# CPLD.net
KiCad netlist of a schematic drawn in Altium Designer
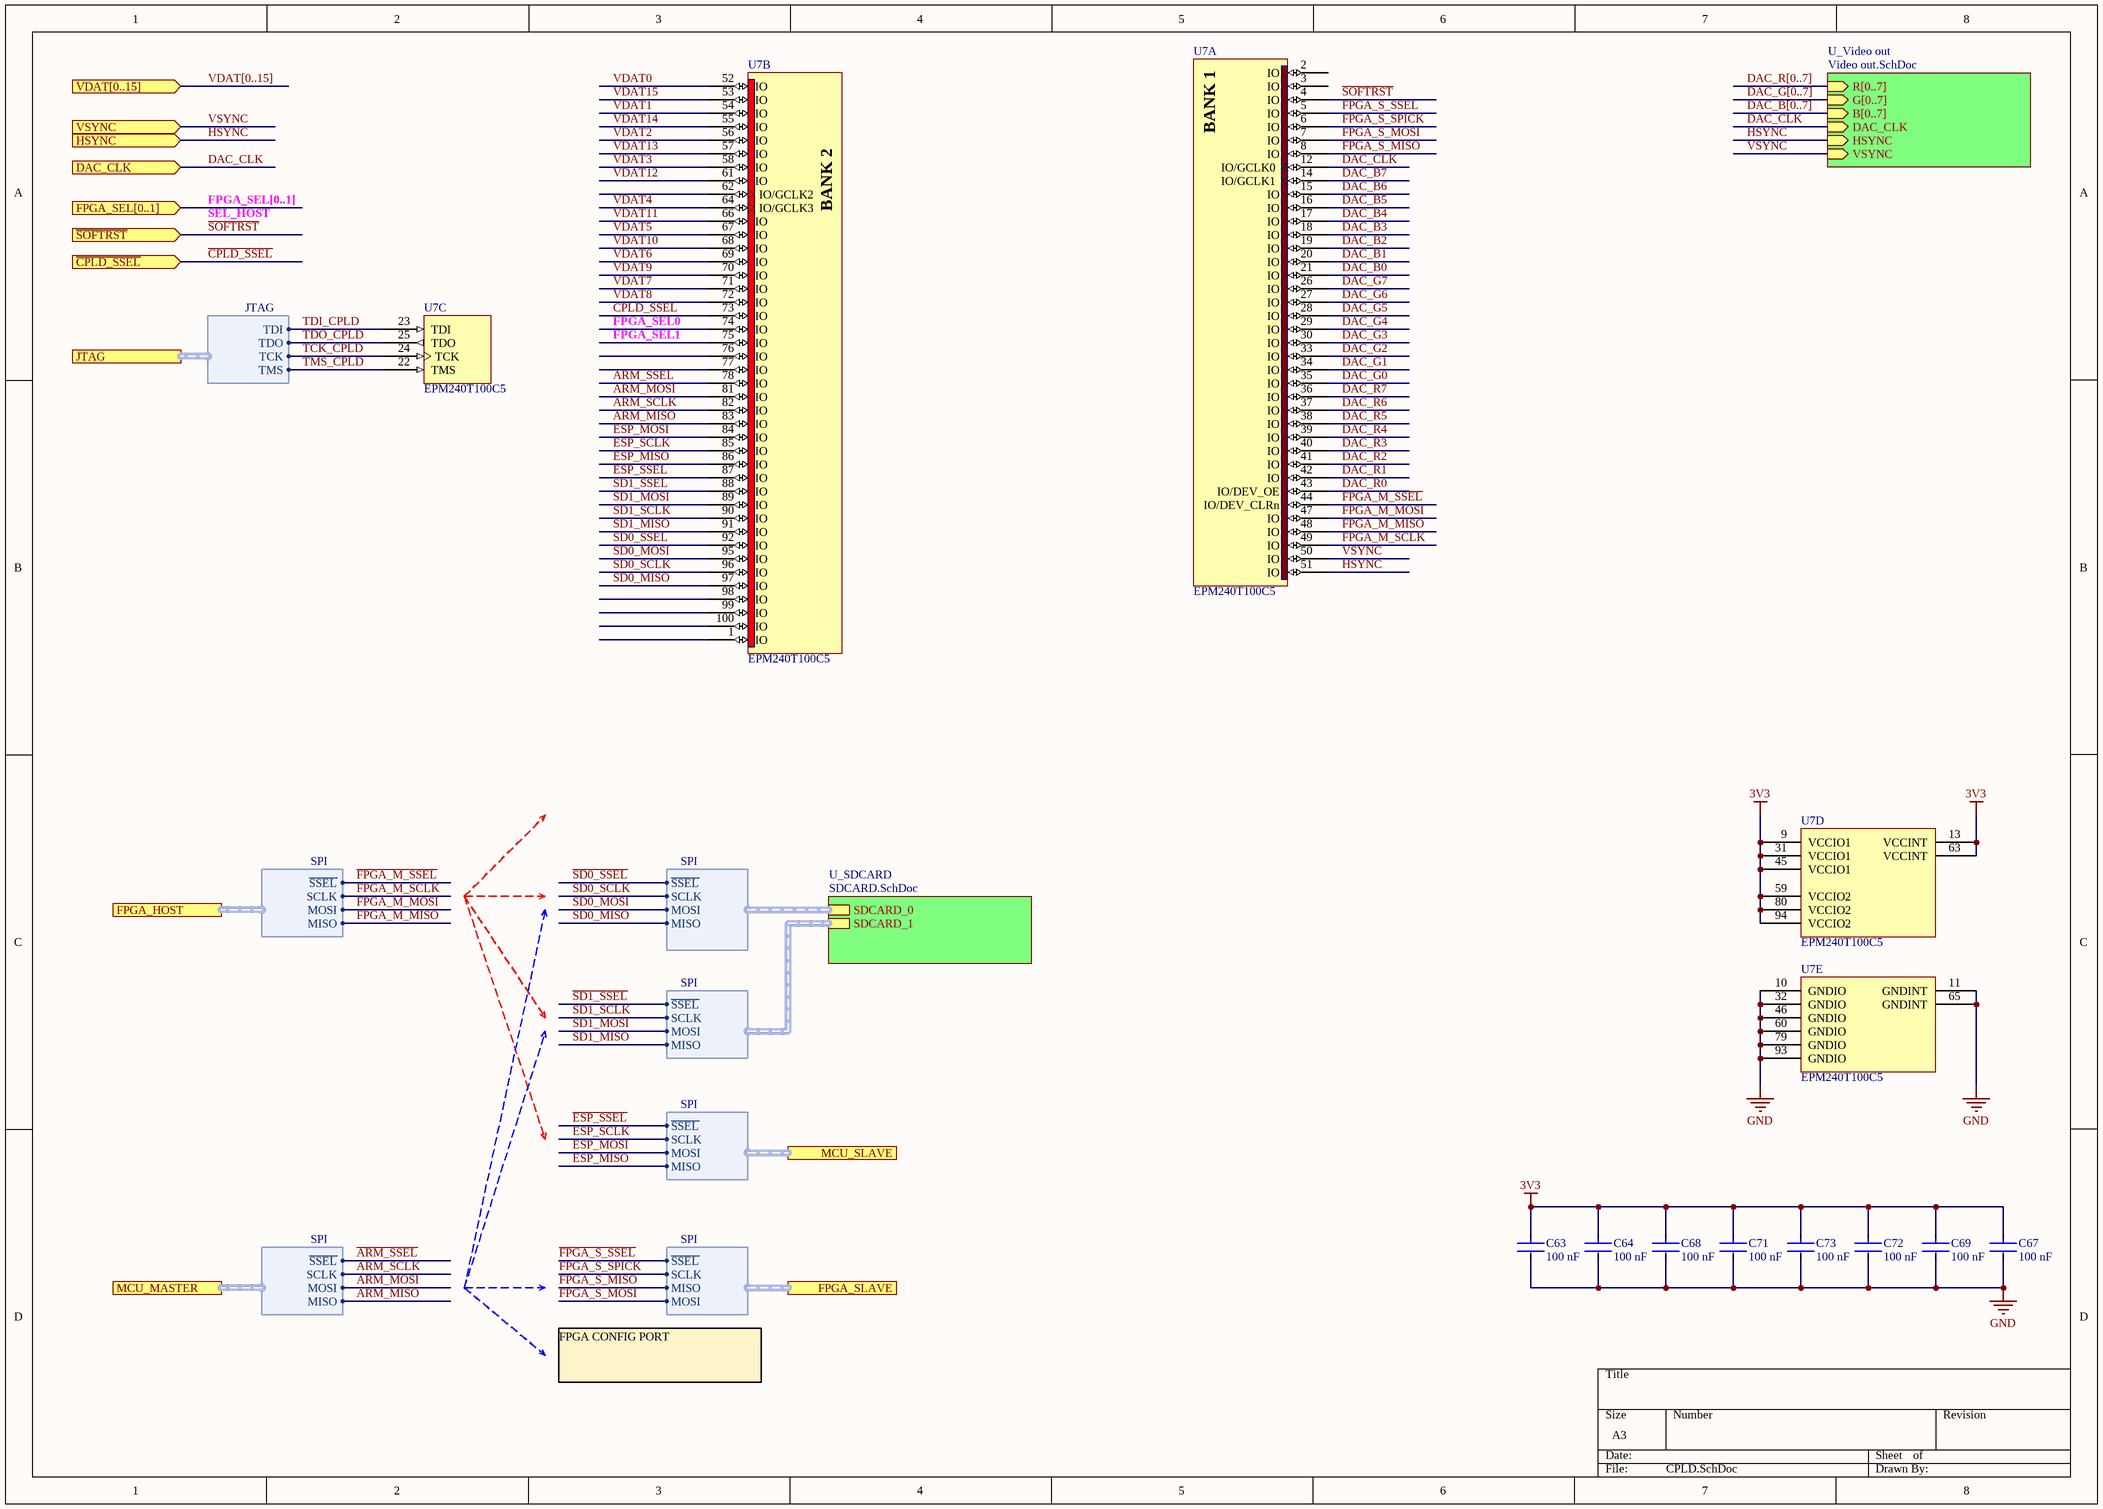
[diagram p0: CPLD.SchDoc]

(export (version "E")
  (design (tool "Eeschema 10.0.6"))
  (components
    (comp (ref "C63")
      (value "CC0805KRX7R9BB104")
      (footprint "FP-CC0805-0_85-IPC_A")
      (description "CAP CER 0.1UF 50V X7R 0805")
      (fields (field (name "MANUFACTURER") "Yageo") (field (name "CAPACITANCE") "100 nF"))
      (libsource (lib "SchLib") (part "CMP-2100-03606-3"))
    )
    (comp (ref "C64")
      (value "CC0805KRX7R9BB104")
      (footprint "FP-CC0805-0_85-IPC_A")
      (description "CAP CER 0.1UF 50V X7R 0805")
      (fields (field (name "MANUFACTURER") "Yageo") (field (name "CAPACITANCE") "100 nF"))
      (libsource (lib "SchLib") (part "CMP-2100-03606-3"))
    )
    (comp (ref "C67")
      (value "CC0805KRX7R9BB104")
      (footprint "FP-CC0805-0_85-IPC_A")
      (description "CAP CER 0.1UF 50V X7R 0805")
      (fields (field (name "MANUFACTURER") "Yageo") (field (name "CAPACITANCE") "100 nF"))
      (libsource (lib "SchLib") (part "CMP-2100-03606-3"))
    )
    (comp (ref "C68")
      (value "CC0805KRX7R9BB104")
      (footprint "FP-CC0805-0_85-IPC_A")
      (description "CAP CER 0.1UF 50V X7R 0805")
      (fields (field (name "MANUFACTURER") "Yageo") (field (name "CAPACITANCE") "100 nF"))
      (libsource (lib "SchLib") (part "CMP-2100-03606-3"))
    )
    (comp (ref "C69")
      (value "CC0805KRX7R9BB104")
      (footprint "FP-CC0805-0_85-IPC_A")
      (description "CAP CER 0.1UF 50V X7R 0805")
      (fields (field (name "MANUFACTURER") "Yageo") (field (name "CAPACITANCE") "100 nF"))
      (libsource (lib "SchLib") (part "CMP-2100-03606-3"))
    )
    (comp (ref "C71")
      (value "CC0805KRX7R9BB104")
      (footprint "FP-CC0805-0_85-IPC_A")
      (description "CAP CER 0.1UF 50V X7R 0805")
      (fields (field (name "MANUFACTURER") "Yageo") (field (name "CAPACITANCE") "100 nF"))
      (libsource (lib "SchLib") (part "CMP-2100-03606-3"))
    )
    (comp (ref "C72")
      (value "CC0805KRX7R9BB104")
      (footprint "FP-CC0805-0_85-IPC_A")
      (description "CAP CER 0.1UF 50V X7R 0805")
      (fields (field (name "MANUFACTURER") "Yageo") (field (name "CAPACITANCE") "100 nF"))
      (libsource (lib "SchLib") (part "CMP-2100-03606-3"))
    )
    (comp (ref "C73")
      (value "CC0805KRX7R9BB104")
      (footprint "FP-CC0805-0_85-IPC_A")
      (description "CAP CER 0.1UF 50V X7R 0805")
      (fields (field (name "MANUFACTURER") "Yageo") (field (name "CAPACITANCE") "100 nF"))
      (libsource (lib "SchLib") (part "CMP-2100-03606-3"))
    )
    (comp (ref "U7")
      (value "EPM240T100C5")
      (footprint "TQFP100_M")
      (fields (field (name "MANUFACTURER") "Intel Altera"))
      (libsource (lib "") (part "CMP-0144-00216-1_1"))
    )
  )
  (nets
    (net (code "3") (name "/ARM_MISO") (class "Default")
      (node (ref "U7") (pin "83") (pinfunction "IO_83") (pintype "bidirectional"))
    )
    (net (code "4") (name "/ARM_MOSI") (class "Default")
      (node (ref "U7") (pin "81") (pinfunction "IO_81") (pintype "bidirectional"))
    )
    (net (code "5") (name "/ARM_SCLK") (class "Default")
      (node (ref "U7") (pin "82") (pinfunction "IO_82") (pintype "bidirectional"))
    )
    (net (code "6") (name "/DAC_B0") (class "Default")
      (node (ref "U7") (pin "21") (pinfunction "IO_21") (pintype "bidirectional"))
    )
    (net (code "7") (name "/DAC_B1") (class "Default")
      (node (ref "U7") (pin "20") (pinfunction "IO_20") (pintype "bidirectional"))
    )
    (net (code "8") (name "/DAC_B2") (class "Default")
      (node (ref "U7") (pin "19") (pinfunction "IO_19") (pintype "bidirectional"))
    )
    (net (code "9") (name "/DAC_B3") (class "Default")
      (node (ref "U7") (pin "18") (pinfunction "IO_18") (pintype "bidirectional"))
    )
    (net (code "10") (name "/DAC_B4") (class "Default")
      (node (ref "U7") (pin "17") (pinfunction "IO_17") (pintype "bidirectional"))
    )
    (net (code "11") (name "/DAC_B5") (class "Default")
      (node (ref "U7") (pin "16") (pinfunction "IO_16") (pintype "bidirectional"))
    )
    (net (code "12") (name "/DAC_B6") (class "Default")
      (node (ref "U7") (pin "15") (pinfunction "IO_15") (pintype "bidirectional"))
    )
    (net (code "13") (name "/DAC_B7") (class "Default")
      (node (ref "U7") (pin "14") (pinfunction "IO/GCLK1_14") (pintype "bidirectional"))
    )
    (net (code "15") (name "/DAC_CLK") (class "Default")
      (node (ref "U7") (pin "12") (pinfunction "IO/GCLK0_12") (pintype "bidirectional"))
    )
    (net (code "16") (name "/DAC_G0") (class "Default")
      (node (ref "U7") (pin "35") (pinfunction "IO_35") (pintype "bidirectional"))
    )
    (net (code "17") (name "/DAC_G1") (class "Default")
      (node (ref "U7") (pin "34") (pinfunction "IO_34") (pintype "bidirectional"))
    )
    (net (code "18") (name "/DAC_G2") (class "Default")
      (node (ref "U7") (pin "33") (pinfunction "IO_33") (pintype "bidirectional"))
    )
    (net (code "19") (name "/DAC_G3") (class "Default")
      (node (ref "U7") (pin "30") (pinfunction "IO_30") (pintype "bidirectional"))
    )
    (net (code "20") (name "/DAC_G4") (class "Default")
      (node (ref "U7") (pin "29") (pinfunction "IO_29") (pintype "bidirectional"))
    )
    (net (code "21") (name "/DAC_G5") (class "Default")
      (node (ref "U7") (pin "28") (pinfunction "IO_28") (pintype "bidirectional"))
    )
    (net (code "22") (name "/DAC_G6") (class "Default")
      (node (ref "U7") (pin "27") (pinfunction "IO_27") (pintype "bidirectional"))
    )
    (net (code "23") (name "/DAC_G7") (class "Default")
      (node (ref "U7") (pin "26") (pinfunction "IO_26") (pintype "bidirectional"))
    )
    (net (code "25") (name "/DAC_R0") (class "Default")
      (node (ref "U7") (pin "43") (pinfunction "IO/DEV_OE_43") (pintype "bidirectional"))
    )
    (net (code "26") (name "/DAC_R1") (class "Default")
      (node (ref "U7") (pin "42") (pinfunction "IO_42") (pintype "bidirectional"))
    )
    (net (code "27") (name "/DAC_R2") (class "Default")
      (node (ref "U7") (pin "41") (pinfunction "IO_41") (pintype "bidirectional"))
    )
    (net (code "28") (name "/DAC_R3") (class "Default")
      (node (ref "U7") (pin "40") (pinfunction "IO_40") (pintype "bidirectional"))
    )
    (net (code "29") (name "/DAC_R4") (class "Default")
      (node (ref "U7") (pin "39") (pinfunction "IO_39") (pintype "bidirectional"))
    )
    (net (code "30") (name "/DAC_R5") (class "Default")
      (node (ref "U7") (pin "38") (pinfunction "IO_38") (pintype "bidirectional"))
    )
    (net (code "31") (name "/DAC_R6") (class "Default")
      (node (ref "U7") (pin "37") (pinfunction "IO_37") (pintype "bidirectional"))
    )
    (net (code "32") (name "/DAC_R7") (class "Default")
      (node (ref "U7") (pin "36") (pinfunction "IO_36") (pintype "bidirectional"))
    )
    (net (code "34") (name "/ESP_MISO") (class "Default")
      (node (ref "U7") (pin "86") (pinfunction "IO_86") (pintype "bidirectional"))
    )
    (net (code "35") (name "/ESP_MOSI") (class "Default")
      (node (ref "U7") (pin "84") (pinfunction "IO_84") (pintype "bidirectional"))
    )
    (net (code "36") (name "/ESP_SCLK") (class "Default")
      (node (ref "U7") (pin "85") (pinfunction "IO_85") (pintype "bidirectional"))
    )
    (net (code "37") (name "/FPGA_M_MISO") (class "Default")
      (node (ref "U7") (pin "48") (pinfunction "IO_48") (pintype "bidirectional"))
    )
    (net (code "38") (name "/FPGA_M_MOSI") (class "Default")
      (node (ref "U7") (pin "47") (pinfunction "IO_47") (pintype "bidirectional"))
    )
    (net (code "39") (name "/FPGA_M_SCLK") (class "Default")
      (node (ref "U7") (pin "49") (pinfunction "IO_49") (pintype "bidirectional"))
    )
    (net (code "40") (name "/FPGA_SEL0") (class "Default")
      (node (ref "U7") (pin "74") (pinfunction "IO_74") (pintype "bidirectional"))
    )
    (net (code "41") (name "/FPGA_SEL1") (class "Default")
      (node (ref "U7") (pin "75") (pinfunction "IO_75") (pintype "bidirectional"))
    )
    (net (code "43") (name "/FPGA_S_MISO") (class "Default")
      (node (ref "U7") (pin "8") (pinfunction "IO_8") (pintype "bidirectional"))
    )
    (net (code "44") (name "/FPGA_S_MOSI") (class "Default")
      (node (ref "U7") (pin "7") (pinfunction "IO_7") (pintype "bidirectional"))
    )
    (net (code "45") (name "/FPGA_S_SPICK") (class "Default")
      (node (ref "U7") (pin "6") (pinfunction "IO_6") (pintype "bidirectional"))
    )
    (net (code "46") (name "/HSYNC") (class "Default")
      (node (ref "U7") (pin "51") (pinfunction "IO_51") (pintype "bidirectional"))
    )
    (net (code "47") (name "/SD0_MISO") (class "Default")
      (node (ref "U7") (pin "97") (pinfunction "IO_97") (pintype "bidirectional"))
    )
    (net (code "48") (name "/SD0_MOSI") (class "Default")
      (node (ref "U7") (pin "95") (pinfunction "IO_95") (pintype "bidirectional"))
    )
    (net (code "49") (name "/SD0_SCLK") (class "Default")
      (node (ref "U7") (pin "96") (pinfunction "IO_96") (pintype "bidirectional"))
    )
    (net (code "50") (name "/SD1_MISO") (class "Default")
      (node (ref "U7") (pin "91") (pinfunction "IO_91") (pintype "bidirectional"))
    )
    (net (code "51") (name "/SD1_MOSI") (class "Default")
      (node (ref "U7") (pin "89") (pinfunction "IO_89") (pintype "bidirectional"))
    )
    (net (code "52") (name "/SD1_SCLK") (class "Default")
      (node (ref "U7") (pin "90") (pinfunction "IO_90") (pintype "bidirectional"))
    )
    (net (code "54") (name "/TCK_CPLD") (class "Default")
      (node (ref "U7") (pin "24") (pinfunction "TCK_24") (pintype "input"))
    )
    (net (code "55") (name "/TDI_CPLD") (class "Default")
      (node (ref "U7") (pin "23") (pinfunction "TDI_23") (pintype "input"))
    )
    (net (code "56") (name "/TDO_CPLD") (class "Default")
      (node (ref "U7") (pin "25") (pinfunction "TDO_25") (pintype "output"))
    )
    (net (code "57") (name "/TMS_CPLD") (class "Default")
      (node (ref "U7") (pin "22") (pinfunction "TMS_22") (pintype "input"))
    )
    (net (code "58") (name "/VDAT0") (class "Default")
      (node (ref "U7") (pin "52") (pinfunction "IO_52") (pintype "bidirectional"))
    )
    (net (code "59") (name "/VDAT1") (class "Default")
      (node (ref "U7") (pin "54") (pinfunction "IO_54") (pintype "bidirectional"))
    )
    (net (code "60") (name "/VDAT2") (class "Default")
      (node (ref "U7") (pin "56") (pinfunction "IO_56") (pintype "bidirectional"))
    )
    (net (code "61") (name "/VDAT3") (class "Default")
      (node (ref "U7") (pin "58") (pinfunction "IO_58") (pintype "bidirectional"))
    )
    (net (code "62") (name "/VDAT4") (class "Default")
      (node (ref "U7") (pin "64") (pinfunction "IO/GCLK3_64") (pintype "bidirectional"))
    )
    (net (code "63") (name "/VDAT5") (class "Default")
      (node (ref "U7") (pin "67") (pinfunction "IO_67") (pintype "bidirectional"))
    )
    (net (code "64") (name "/VDAT6") (class "Default")
      (node (ref "U7") (pin "69") (pinfunction "IO_69") (pintype "bidirectional"))
    )
    (net (code "65") (name "/VDAT7") (class "Default")
      (node (ref "U7") (pin "71") (pinfunction "IO_71") (pintype "bidirectional"))
    )
    (net (code "66") (name "/VDAT8") (class "Default")
      (node (ref "U7") (pin "72") (pinfunction "IO_72") (pintype "bidirectional"))
    )
    (net (code "67") (name "/VDAT9") (class "Default")
      (node (ref "U7") (pin "70") (pinfunction "IO_70") (pintype "bidirectional"))
    )
    (net (code "68") (name "/VDAT10") (class "Default")
      (node (ref "U7") (pin "68") (pinfunction "IO_68") (pintype "bidirectional"))
    )
    (net (code "69") (name "/VDAT11") (class "Default")
      (node (ref "U7") (pin "66") (pinfunction "IO_66") (pintype "bidirectional"))
    )
    (net (code "70") (name "/VDAT12") (class "Default")
      (node (ref "U7") (pin "61") (pinfunction "IO_61") (pintype "bidirectional"))
    )
    (net (code "71") (name "/VDAT13") (class "Default")
      (node (ref "U7") (pin "57") (pinfunction "IO_57") (pintype "bidirectional"))
    )
    (net (code "72") (name "/VDAT14") (class "Default")
      (node (ref "U7") (pin "55") (pinfunction "IO_55") (pintype "bidirectional"))
    )
    (net (code "73") (name "/VDAT15") (class "Default")
      (node (ref "U7") (pin "53") (pinfunction "IO_53") (pintype "bidirectional"))
    )
    (net (code "75") (name "/VSYNC") (class "Default")
      (node (ref "U7") (pin "50") (pinfunction "IO_50") (pintype "bidirectional"))
    )
    (net (code "78") (name "/~{ARM_SSEL}") (class "Default")
      (node (ref "U7") (pin "78") (pinfunction "IO_78") (pintype "bidirectional"))
    )
    (net (code "79") (name "/~{CPLD_SSEL}") (class "Default")
      (node (ref "U7") (pin "73") (pinfunction "IO_73") (pintype "bidirectional"))
    )
    (net (code "80") (name "/~{ESP_SSEL}") (class "Default")
      (node (ref "U7") (pin "87") (pinfunction "IO_87") (pintype "bidirectional"))
    )
    (net (code "81") (name "/~{FPGA_M_SSEL}") (class "Default")
      (node (ref "U7") (pin "44") (pinfunction "IO/DEV_CLRn_44") (pintype "bidirectional"))
    )
    (net (code "82") (name "/~{FPGA_S_SSEL}") (class "Default")
      (node (ref "U7") (pin "5") (pinfunction "IO_5") (pintype "bidirectional"))
    )
    (net (code "83") (name "/~{SD0_SSEL}") (class "Default")
      (node (ref "U7") (pin "92") (pinfunction "IO_92") (pintype "bidirectional"))
    )
    (net (code "84") (name "/~{SD1_SSEL}") (class "Default")
      (node (ref "U7") (pin "88") (pinfunction "IO_88") (pintype "bidirectional"))
    )
    (net (code "85") (name "/~{SOFTRST}") (class "Default")
      (node (ref "U7") (pin "4") (pinfunction "IO_4") (pintype "bidirectional"))
    )
    (net (code "86") (name "3V3") (class "Default")
      (node (ref "C63") (pin "1") (pinfunction "1_1") (pintype "passive"))
      (node (ref "C64") (pin "1") (pinfunction "1_1") (pintype "passive"))
      (node (ref "C67") (pin "1") (pinfunction "1_1") (pintype "passive"))
      (node (ref "C68") (pin "1") (pinfunction "1_1") (pintype "passive"))
      (node (ref "C69") (pin "1") (pinfunction "1_1") (pintype "passive"))
      (node (ref "C71") (pin "1") (pinfunction "1_1") (pintype "passive"))
      (node (ref "C72") (pin "1") (pinfunction "1_1") (pintype "passive"))
      (node (ref "C73") (pin "1") (pinfunction "1_1") (pintype "passive"))
      (node (ref "U7") (pin "13") (pinfunction "VCCINT_13") (pintype "power_in"))
      (node (ref "U7") (pin "31") (pinfunction "VCCIO1_31") (pintype "power_in"))
      (node (ref "U7") (pin "45") (pinfunction "VCCIO1_45") (pintype "power_in"))
      (node (ref "U7") (pin "59") (pinfunction "VCCIO2_59") (pintype "power_in"))
      (node (ref "U7") (pin "63") (pinfunction "VCCINT_63") (pintype "power_in"))
      (node (ref "U7") (pin "80") (pinfunction "VCCIO2_80") (pintype "power_in"))
      (node (ref "U7") (pin "9") (pinfunction "VCCIO1_9") (pintype "power_in"))
      (node (ref "U7") (pin "94") (pinfunction "VCCIO2_94") (pintype "power_in"))
    )
    (net (code "87") (name "GND") (class "Default")
      (node (ref "C63") (pin "2") (pinfunction "2_2") (pintype "passive"))
      (node (ref "C64") (pin "2") (pinfunction "2_2") (pintype "passive"))
      (node (ref "C67") (pin "2") (pinfunction "2_2") (pintype "passive"))
      (node (ref "C68") (pin "2") (pinfunction "2_2") (pintype "passive"))
      (node (ref "C69") (pin "2") (pinfunction "2_2") (pintype "passive"))
      (node (ref "C71") (pin "2") (pinfunction "2_2") (pintype "passive"))
      (node (ref "C72") (pin "2") (pinfunction "2_2") (pintype "passive"))
      (node (ref "C73") (pin "2") (pinfunction "2_2") (pintype "passive"))
      (node (ref "U7") (pin "10") (pinfunction "GNDIO_10") (pintype "power_in"))
      (node (ref "U7") (pin "11") (pinfunction "GNDINT_11") (pintype "power_in"))
      (node (ref "U7") (pin "32") (pinfunction "GNDIO_32") (pintype "power_in"))
      (node (ref "U7") (pin "46") (pinfunction "GNDIO_46") (pintype "power_in"))
      (node (ref "U7") (pin "60") (pinfunction "GNDIO_60") (pintype "power_in"))
      (node (ref "U7") (pin "65") (pinfunction "GNDINT_65") (pintype "power_in"))
      (node (ref "U7") (pin "79") (pinfunction "GNDIO_79") (pintype "power_in"))
      (node (ref "U7") (pin "93") (pinfunction "GNDIO_93") (pintype "power_in"))
    )
    (net (code "88") (name "unconnected-(U7A-IO-Pad2)") (class "Default")
      (node (ref "U7") (pin "2") (pinfunction "IO_2") (pintype "bidirectional"))
    )
    (net (code "89") (name "unconnected-(U7A-IO-Pad3)") (class "Default")
      (node (ref "U7") (pin "3") (pinfunction "IO_3") (pintype "bidirectional"))
    )
    (net (code "90") (name "unconnected-(U7B-IO-Pad1)") (class "Default")
      (node (ref "U7") (pin "1") (pinfunction "IO_1") (pintype "bidirectional"))
    )
    (net (code "91") (name "unconnected-(U7B-IO-Pad76)") (class "Default")
      (node (ref "U7") (pin "76") (pinfunction "IO_76") (pintype "bidirectional"))
    )
    (net (code "92") (name "unconnected-(U7B-IO-Pad77)") (class "Default")
      (node (ref "U7") (pin "77") (pinfunction "IO_77") (pintype "bidirectional"))
    )
    (net (code "93") (name "unconnected-(U7B-IO-Pad98)") (class "Default")
      (node (ref "U7") (pin "98") (pinfunction "IO_98") (pintype "bidirectional"))
    )
    (net (code "94") (name "unconnected-(U7B-IO-Pad99)") (class "Default")
      (node (ref "U7") (pin "99") (pinfunction "IO_99") (pintype "bidirectional"))
    )
    (net (code "95") (name "unconnected-(U7B-IO-Pad100)") (class "Default")
      (node (ref "U7") (pin "100") (pinfunction "IO_100") (pintype "bidirectional"))
    )
    (net (code "96") (name "unconnected-(U7B-IO{slash}GCLK2-Pad62)") (class "Default")
      (node (ref "U7") (pin "62") (pinfunction "IO/GCLK2_62") (pintype "bidirectional"))
    )
  )
)
